# POW_Schematic4.net
KiCad netlist of a schematic drawn in Altium Designer
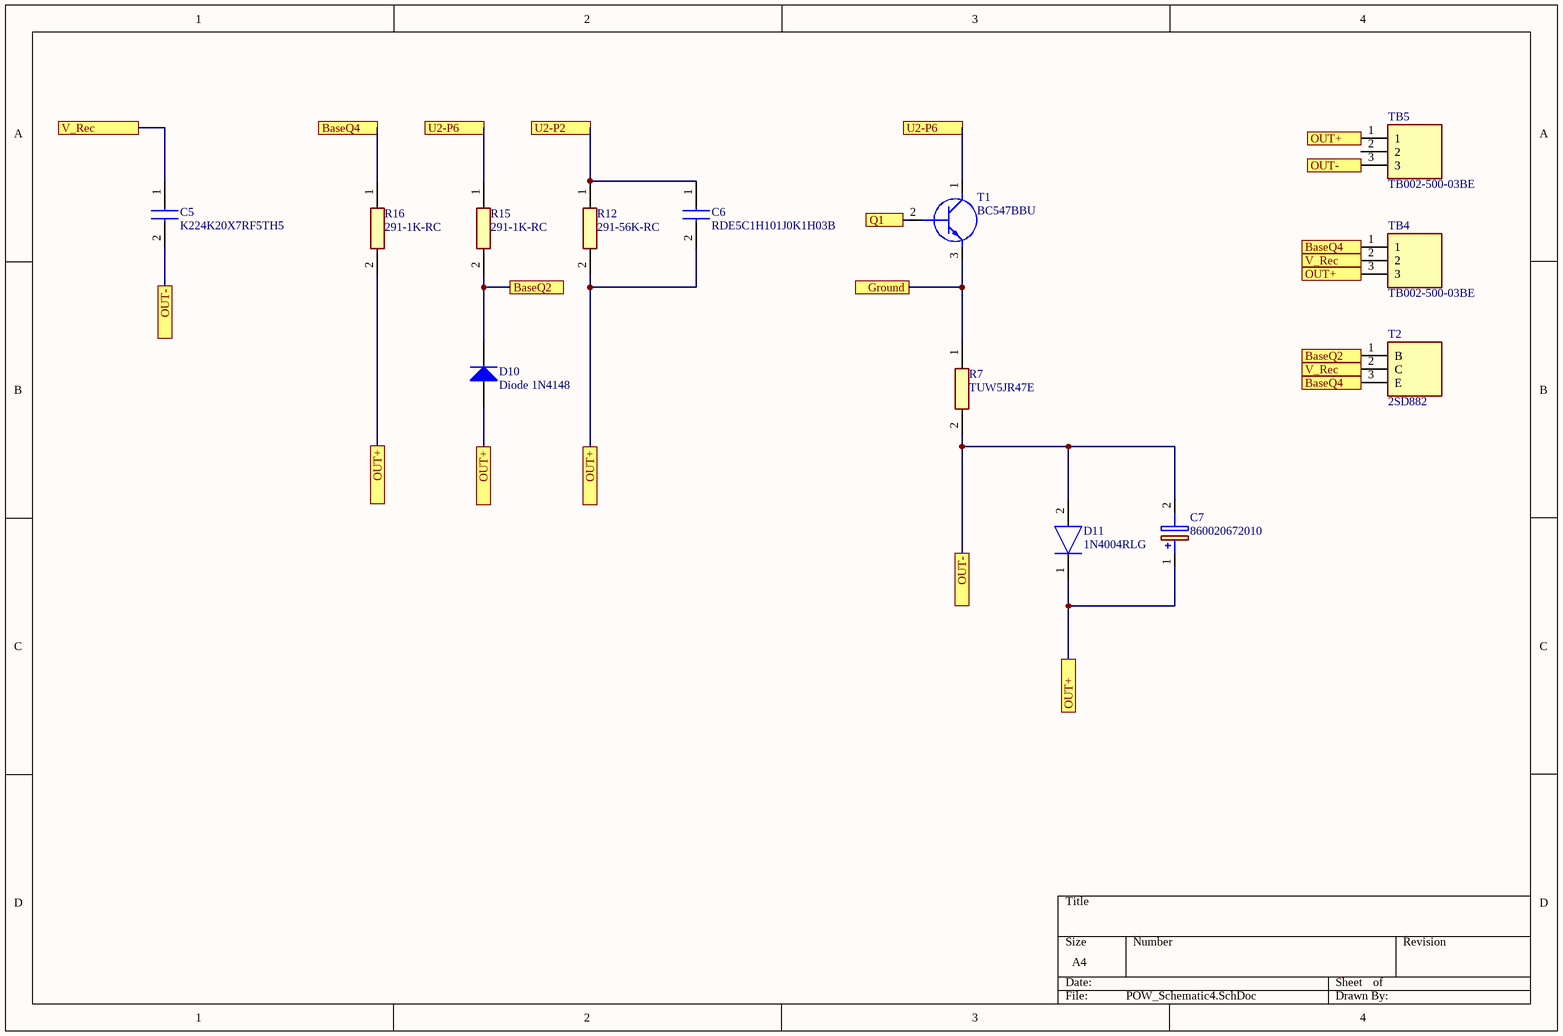
[diagram p0: POW_Schematic4.SchDoc]

(export (version "E")
  (design (tool "Eeschema 10.0.6"))
  (components
    (comp (ref "C5")
      (value "K224K20X7RF5TH5")
      (footprint "K224K20X7RF5TH5")
      (description "Capacitor")
      (fields
        (field (name "MOUSER PART NUMBER") "594-K224K20X7RF5TH5")
        (field (name "RS PART NUMBER") "8523328")
      )
      (libsource (lib "Schlib_POW_HugoHamblok") (part "K224K20X7RF5TH5"))
    )
    (comp (ref "C6")
      (value "RDE5C1H101J0K1H03B")
      (footprint "RCE5C1H103J1A2H03B")
      (description "Capacitor")
      (fields (field (name "MOUSER PART NUMBER") "81-RDE5C1H101J0K1H3B"))
      (libsource (lib "Schlib_POW_HugoHamblok") (part "RDE5C1H101J0K1H03B"))
    )
    (comp (ref "C7")
      (value "860020672010")
      (footprint "CAPPRD200W52D500H1250")
      (description "Capacitor Polarised")
      (fields
        (field (name "MOUSER PART NUMBER") "710-860020672010")
        (field (name "RS PART NUMBER") "8396621P")
      )
      (libsource (lib "Schlib_POW_HugoHamblok") (part "860020672010"))
    )
    (comp (ref "D10")
      (value "Diode 1N4148")
      (footprint "DO-35")
      (description "High Conductance Fast Diode")
      (fields (field (name "PUBLISHER") "Altium Limited"))
      (libsource (lib "Miscellaneous Devices") (part "Diode 1N4148"))
    )
    (comp (ref "D11")
      (value "1N4004RLG")
      (footprint "DIOAD1405W86L465D235")
      (description "Diode")
      (fields (field (name "MOUSER PART NUMBER") "863-1N4004RLG") (field (name "RS PART NUMBER") "1844627P"))
      (libsource (lib "Schlib_POW_HugoHamblok") (part "1N4004RLG"))
    )
    (comp (ref "R7")
      (value "TUW5JR47E")
      (footprint "TUW5JR47E")
      (description "Resistor")
      (fields (field (name "MOUSER PART NUMBER") "588-TUW5JR47E") (field (name "RS PART NUMBER") "8934166"))
      (libsource (lib "Schlib_POW_HugoHamblok") (part "TUW5JR47E"))
    )
    (comp (ref "R12")
      (value "291-56K-RC")
      (footprint "291-XXX-RC-Type")
      (libsource (lib "Schlib_POW_HugoHamblok") (part "291-56K-RC"))
    )
    (comp (ref "R15")
      (value "291-1K-RC")
      (footprint "291-XXX-RC-Type")
      (libsource (lib "Schlib_POW_HugoHamblok") (part "291-1K-RC"))
    )
    (comp (ref "R16")
      (value "291-1K-RC")
      (footprint "291-XXX-RC-Type")
      (libsource (lib "Schlib_POW_HugoHamblok") (part "291-1K-RC"))
    )
    (comp (ref "T1")
      (value "BC547BBU")
      (footprint "PcbLib_POW_HugoHamblok:SS9018HBU")
      (description "Transistor BJT NPN")
      (fields (field (name "MOUSER PART NUMBER") "512-BC547BBU") (field (name "RS PART NUMBER") "8031083P"))
      (libsource (lib "Schlib_POW_HugoHamblok") (part "BC547BBU"))
    )
    (comp (ref "T2")
      (value "2SD882")
      (footprint "TO254P290X760X1320-3P")
      (description "Integrated Circuit")
      (fields (field (name "MOUSER PART NUMBER") "511-2SD882") (field (name "RS PART NUMBER") "6868045P"))
      (libsource (lib "Schlib_POW_HugoHamblok") (part "2SD882"))
    )
    (comp (ref "TB4")
      (value "TB002-500-03BE")
      (footprint "SHDR3W100P0X500_1X3_1500X760X1000P")
      (description "Connector")
      (fields (field (name "MOUSER PART NUMBER") "490-TB002-500-03BE"))
      (libsource (lib "Schlib_POW_HugoHamblok") (part "TB002-500-03BE"))
    )
    (comp (ref "TB5")
      (value "TB002-500-03BE")
      (footprint "SHDR3W100P0X500_1X3_1500X760X1000P")
      (description "Connector")
      (fields (field (name "MOUSER PART NUMBER") "490-TB002-500-03BE"))
      (libsource (lib "Schlib_POW_HugoHamblok") (part "TB002-500-03BE"))
    )
  )
  (nets
    (net (code "1") (name "/BaseQ2") (class "Default")
      (node (ref "D10") (pin "2") (pinfunction "K_2") (pintype "passive"))
      (node (ref "R15") (pin "2") (pinfunction "2_2") (pintype "passive"))
      (node (ref "T2") (pin "1") (pinfunction "B_1") (pintype "passive"))
    )
    (net (code "2") (name "/BaseQ4") (class "Default")
      (node (ref "R16") (pin "1") (pinfunction "1_1") (pintype "passive"))
      (node (ref "T2") (pin "3") (pinfunction "E_3") (pintype "passive"))
      (node (ref "TB4") (pin "1") (pinfunction "1_1") (pintype "passive"))
    )
    (net (code "3") (name "/Ground") (class "Default")
      (node (ref "R7") (pin "1") (pinfunction "1_1") (pintype "passive"))
      (node (ref "T1") (pin "3") (pinfunction "E_3") (pintype "passive"))
    )
    (net (code "4") (name "/OUT+") (class "Default")
      (node (ref "C6") (pin "2") (pinfunction "2_2") (pintype "passive"))
      (node (ref "C7") (pin "1") (pinfunction "+_1") (pintype "passive"))
      (node (ref "D10") (pin "1") (pinfunction "A_1") (pintype "passive"))
      (node (ref "D11") (pin "1") (pinfunction "K_1") (pintype "passive"))
      (node (ref "R12") (pin "2") (pinfunction "2_2") (pintype "passive"))
      (node (ref "R16") (pin "2") (pinfunction "2_2") (pintype "passive"))
      (node (ref "TB4") (pin "3") (pinfunction "3_3") (pintype "passive"))
      (node (ref "TB5") (pin "1") (pinfunction "1_1") (pintype "passive"))
    )
    (net (code "5") (name "/OUT-") (class "Default")
      (node (ref "C5") (pin "2") (pinfunction "2_2") (pintype "passive"))
      (node (ref "C7") (pin "2") (pinfunction "-_2") (pintype "passive"))
      (node (ref "D11") (pin "2") (pinfunction "A_2") (pintype "passive"))
      (node (ref "R7") (pin "2") (pinfunction "2_2") (pintype "passive"))
      (node (ref "TB5") (pin "3") (pinfunction "3_3") (pintype "passive"))
    )
    (net (code "6") (name "/Q1") (class "Default")
      (node (ref "T1") (pin "2") (pinfunction "B_2") (pintype "passive"))
    )
    (net (code "7") (name "/U2-P2") (class "Default")
      (node (ref "C6") (pin "1") (pinfunction "1_1") (pintype "passive"))
      (node (ref "R12") (pin "1") (pinfunction "1_1") (pintype "passive"))
    )
    (net (code "8") (name "/U2-P6") (class "Default")
      (node (ref "R15") (pin "1") (pinfunction "1_1") (pintype "passive"))
      (node (ref "T1") (pin "1") (pinfunction "C_1") (pintype "passive"))
    )
    (net (code "9") (name "/V_Rec") (class "Default")
      (node (ref "C5") (pin "1") (pinfunction "1_1") (pintype "passive"))
      (node (ref "T2") (pin "2") (pinfunction "C_2") (pintype "passive"))
      (node (ref "TB4") (pin "2") (pinfunction "2_2") (pintype "passive"))
    )
    (net (code "10") (name "unconnected-(TB5-Pad2)") (class "Default")
      (node (ref "TB5") (pin "2") (pinfunction "2_2") (pintype "passive"))
    )
  )
)
